# dcc-promicro.net
KiCad netlist of a schematic drawn in EAGLE
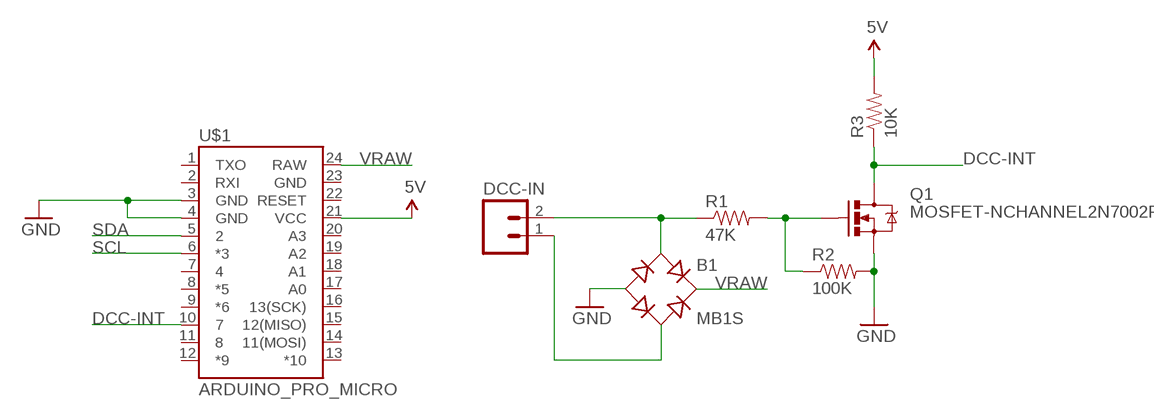
[diagram p0: schematic, sheet 1]

(export (version "E")
  (design (tool "Eeschema 10.0.6"))
  (components
    (comp (ref "B1")
      (value "MB1S")
      (footprint "eagle-import:SOIC-4")
      (libsource (lib "eagle-import") (part "MBS1"))
    )
    (comp (ref "DCC-IN")
      (value "M02PTH")
      (footprint "eagle-import:1X02")
      (libsource (lib "eagle-import") (part "M02PTH"))
    )
    (comp (ref "Q1")
      (value "MOSFET-NCHANNEL2N7002PW")
      (footprint "eagle-import:SOT323")
      (libsource (lib "eagle-import") (part "MOSFET-NCHANNEL2N7002PW"))
    )
    (comp (ref "R1")
      (value "47K")
      (footprint "eagle-import:0603-RES")
      (libsource (lib "eagle-import") (part "RESISTOR0603-RES"))
    )
    (comp (ref "R2")
      (value "100K")
      (footprint "eagle-import:0603-RES")
      (libsource (lib "eagle-import") (part "RESISTOR0603-RES"))
    )
    (comp (ref "R3")
      (value "10K")
      (footprint "eagle-import:0603-RES")
      (libsource (lib "eagle-import") (part "RESISTOR0603-RES"))
    )
    (comp (ref "U$1")
      (value "ARDUINO_PRO_MICRO")
      (footprint "eagle-import:ARDUINO_PRO_MICRO")
      (libsource (lib "eagle-import") (part "ARDUINO_PRO_MICRO"))
    )
  )
  (nets
    (net (code "1") (name "/DCC-INT") (class "Default")
      (node (ref "Q1") (pin "3") (pinfunction "D_3") (pintype "passive"))
      (node (ref "R3") (pin "1") (pinfunction "1_1") (pintype "passive"))
      (node (ref "U$1") (pin "10") (pinfunction "7_10") (pintype "bidirectional"))
    )
    (net (code "2") (name "/SCL") (class "Default")
      (node (ref "U$1") (pin "6") (pinfunction "*3_6") (pintype "bidirectional"))
    )
    (net (code "3") (name "/SDA") (class "Default")
      (node (ref "U$1") (pin "5") (pinfunction "2_5") (pintype "bidirectional"))
    )
    (net (code "4") (name "/VRAW") (class "Default")
      (node (ref "B1") (pin "+") (pinfunction "+_+") (pintype "passive"))
      (node (ref "U$1") (pin "24") (pinfunction "RAW_24") (pintype "bidirectional"))
    )
    (net (code "5") (name "5V") (class "Default")
      (node (ref "R3") (pin "2") (pinfunction "2_2") (pintype "passive"))
      (node (ref "U$1") (pin "21") (pinfunction "VCC_21") (pintype "bidirectional"))
    )
    (net (code "6") (name "GND") (class "Default")
      (node (ref "B1") (pin "-") (pinfunction "-_-") (pintype "passive"))
      (node (ref "Q1") (pin "2") (pinfunction "S_2") (pintype "passive"))
      (node (ref "R2") (pin "2") (pinfunction "2_2") (pintype "passive"))
      (node (ref "U$1") (pin "3") (pinfunction "GND_3") (pintype "bidirectional"))
      (node (ref "U$1") (pin "4") (pinfunction "GND_4") (pintype "bidirectional"))
    )
    (net (code "7") (name "Net-(B1-AC1)") (class "Default")
      (node (ref "B1") (pin "~1") (pinfunction "AC1_~1") (pintype "passive"))
      (node (ref "DCC-IN") (pin "2") (pinfunction "2_2") (pintype "passive"))
      (node (ref "R1") (pin "1") (pinfunction "1_1") (pintype "passive"))
    )
    (net (code "8") (name "Net-(B1-AC2)") (class "Default")
      (node (ref "B1") (pin "~2") (pinfunction "AC2_~2") (pintype "passive"))
      (node (ref "DCC-IN") (pin "1") (pinfunction "1_1") (pintype "passive"))
    )
    (net (code "9") (name "Net-(Q1-G)") (class "Default")
      (node (ref "Q1") (pin "1") (pinfunction "G_1") (pintype "passive"))
      (node (ref "R1") (pin "2") (pinfunction "2_2") (pintype "passive"))
      (node (ref "R2") (pin "1") (pinfunction "1_1") (pintype "passive"))
    )
    (net (code "10") (name "unconnected-(U$1-*5-Pad8)") (class "Default")
      (node (ref "U$1") (pin "8") (pinfunction "*5_8") (pintype "bidirectional"))
    )
    (net (code "11") (name "unconnected-(U$1-*6-Pad9)") (class "Default")
      (node (ref "U$1") (pin "9") (pinfunction "*6_9") (pintype "bidirectional"))
    )
    (net (code "12") (name "unconnected-(U$1-*9-Pad12)") (class "Default")
      (node (ref "U$1") (pin "12") (pinfunction "*9_12") (pintype "bidirectional"))
    )
    (net (code "13") (name "unconnected-(U$1-*10-Pad13)") (class "Default")
      (node (ref "U$1") (pin "13") (pinfunction "*10_13") (pintype "bidirectional"))
    )
    (net (code "14") (name "unconnected-(U$1-4-Pad7)") (class "Default")
      (node (ref "U$1") (pin "7") (pinfunction "4_7") (pintype "bidirectional"))
    )
    (net (code "15") (name "unconnected-(U$1-8-Pad11)") (class "Default")
      (node (ref "U$1") (pin "11") (pinfunction "8_11") (pintype "bidirectional"))
    )
    (net (code "16") (name "unconnected-(U$1-11(MOSI)-Pad14)") (class "Default")
      (node (ref "U$1") (pin "14") (pinfunction "11(MOSI)_14") (pintype "bidirectional"))
    )
    (net (code "17") (name "unconnected-(U$1-12(MISO)-Pad15)") (class "Default")
      (node (ref "U$1") (pin "15") (pinfunction "12(MISO)_15") (pintype "bidirectional"))
    )
    (net (code "18") (name "unconnected-(U$1-13(SCK)-Pad16)") (class "Default")
      (node (ref "U$1") (pin "16") (pinfunction "13(SCK)_16") (pintype "bidirectional"))
    )
    (net (code "19") (name "unconnected-(U$1-A0-Pad17)") (class "Default")
      (node (ref "U$1") (pin "17") (pinfunction "A0_17") (pintype "bidirectional"))
    )
    (net (code "20") (name "unconnected-(U$1-A1-Pad18)") (class "Default")
      (node (ref "U$1") (pin "18") (pinfunction "A1_18") (pintype "bidirectional"))
    )
    (net (code "21") (name "unconnected-(U$1-A2-Pad19)") (class "Default")
      (node (ref "U$1") (pin "19") (pinfunction "A2_19") (pintype "bidirectional"))
    )
    (net (code "22") (name "unconnected-(U$1-A3-Pad20)") (class "Default")
      (node (ref "U$1") (pin "20") (pinfunction "A3_20") (pintype "bidirectional"))
    )
    (net (code "23") (name "unconnected-(U$1-GND-Pad23)") (class "Default")
      (node (ref "U$1") (pin "23") (pinfunction "GND_23") (pintype "bidirectional"))
    )
    (net (code "24") (name "unconnected-(U$1-RESET-Pad22)") (class "Default")
      (node (ref "U$1") (pin "22") (pinfunction "RESET_22") (pintype "bidirectional"))
    )
    (net (code "25") (name "unconnected-(U$1-RXI-Pad2)") (class "Default")
      (node (ref "U$1") (pin "2") (pinfunction "RXI_2") (pintype "bidirectional"))
    )
    (net (code "26") (name "unconnected-(U$1-TXO-Pad1)") (class "Default")
      (node (ref "U$1") (pin "1") (pinfunction "TXO_1") (pintype "bidirectional"))
    )
  )
)
